# Sensor_Board_2_02_HX711_DS18b2.net
KiCad netlist of a schematic drawn in EAGLE
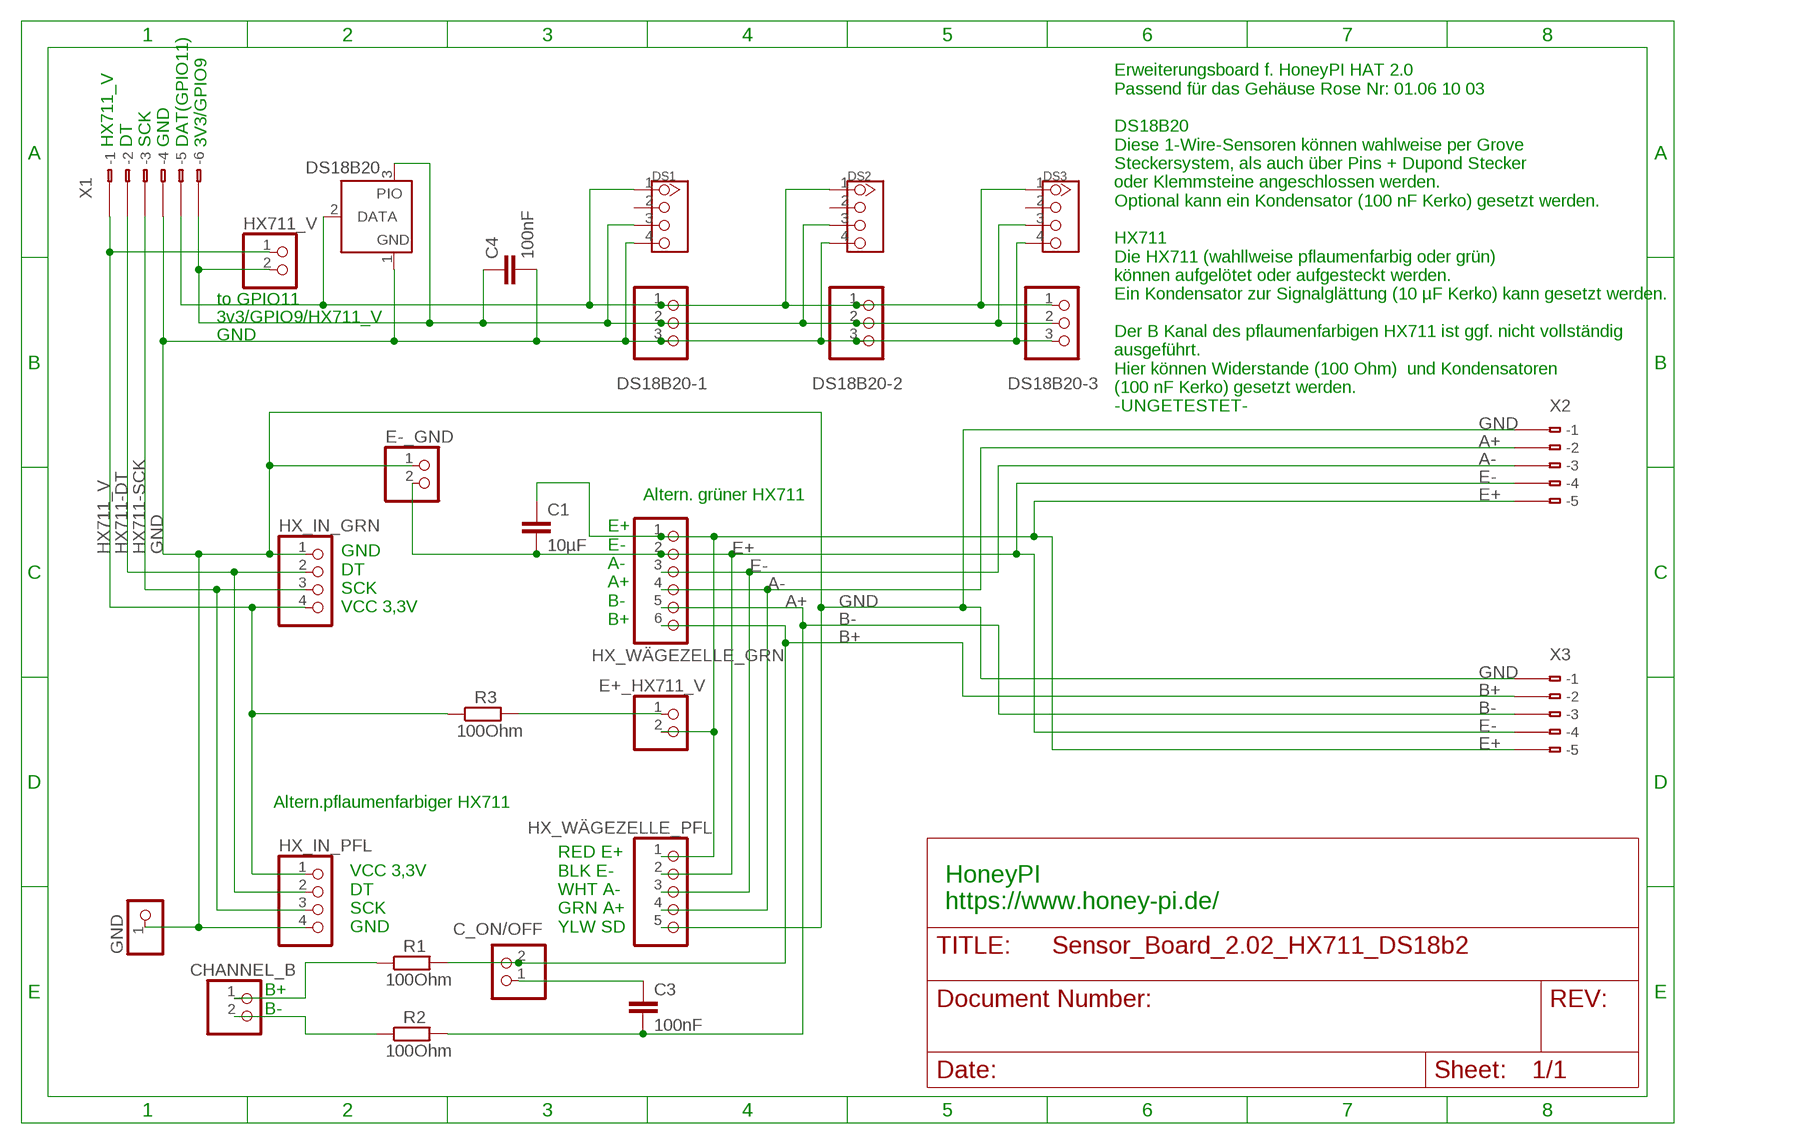
[diagram p0: schematic, sheet 1]

(export (version "E")
  (design (tool "Eeschema 10.0.6"))
  (components
    (comp (ref "C1")
      (value "10µF")
      (footprint "eagle-import:C5B2.5")
      (libsource (lib "eagle-import") (part "C5/2.5"))
    )
    (comp (ref "C3")
      (value "100nF")
      (footprint "eagle-import:C5B2.5")
      (libsource (lib "eagle-import") (part "C5/2.5"))
    )
    (comp (ref "C4")
      (value "100nF")
      (footprint "eagle-import:C5B2.5")
      (libsource (lib "eagle-import") (part "C5/2.5"))
    )
    (comp (ref "CHANNEL_B")
      (value "PINHD-1X2")
      (footprint "eagle-import:1X02")
      (libsource (lib "eagle-import") (part "PINHD-1X2"))
    )
    (comp (ref "C_ON/OFF")
      (value "PINHD-1X2")
      (footprint "eagle-import:1X02")
      (libsource (lib "eagle-import") (part "PINHD-1X2"))
    )
    (comp (ref "DS1")
      (value "TWIG-4P-2.0-2.0")
      (footprint "eagle-import:4P-2.0")
      (libsource (lib "eagle-import") (part "TWIG-4P-2.0-2.0"))
    )
    (comp (ref "DS2")
      (value "TWIG-4P-2.0-2.0")
      (footprint "eagle-import:4P-2.0")
      (libsource (lib "eagle-import") (part "TWIG-4P-2.0-2.0"))
    )
    (comp (ref "DS3")
      (value "TWIG-4P-2.0-2.0")
      (footprint "eagle-import:4P-2.0")
      (libsource (lib "eagle-import") (part "TWIG-4P-2.0-2.0"))
    )
    (comp (ref "DS18B20")
      (value "DS2405")
      (footprint "eagle-import:TO92-")
      (fields (field (name "MF") "DALLAS SEMICONDUCTOR"))
      (libsource (lib "eagle-import") (part "DS2405"))
    )
    (comp (ref "DS18B20-1")
      (value "PINHD-1X3")
      (footprint "eagle-import:1X03")
      (libsource (lib "eagle-import") (part "PINHD-1X3"))
    )
    (comp (ref "DS18B20-2")
      (value "PINHD-1X3")
      (footprint "eagle-import:1X03")
      (libsource (lib "eagle-import") (part "PINHD-1X3"))
    )
    (comp (ref "DS18B20-3")
      (value "PINHD-1X3")
      (footprint "eagle-import:1X03")
      (libsource (lib "eagle-import") (part "PINHD-1X3"))
    )
    (comp (ref "E+_HX711_V")
      (value "PINHD-1X2")
      (footprint "eagle-import:1X02")
      (libsource (lib "eagle-import") (part "PINHD-1X2"))
    )
    (comp (ref "E-_GND")
      (value "PINHD-1X2")
      (footprint "eagle-import:1X02")
      (libsource (lib "eagle-import") (part "PINHD-1X2"))
    )
    (comp (ref "GND")
      (value "PINHD-1X1")
      (footprint "eagle-import:1X01")
      (libsource (lib "eagle-import") (part "PINHD-1X1"))
    )
    (comp (ref "HX711_V")
      (value "PINHD-1X2")
      (footprint "eagle-import:1X02")
      (libsource (lib "eagle-import") (part "PINHD-1X2"))
    )
    (comp (ref "HX_IN_GRN")
      (value "PINHD-1X4")
      (footprint "eagle-import:1X04")
      (libsource (lib "eagle-import") (part "PINHD-1X4"))
    )
    (comp (ref "HX_IN_PFL")
      (value "PINHD-1X4")
      (footprint "eagle-import:1X04")
      (libsource (lib "eagle-import") (part "PINHD-1X4"))
    )
    (comp (ref "HX_WÄGEZELLE_GRN")
      (value "PINHD-1X6")
      (footprint "eagle-import:1X06")
      (libsource (lib "eagle-import") (part "PINHD-1X6"))
    )
    (comp (ref "HX_WÄGEZELLE_PFL")
      (value "PINHD-1X5")
      (footprint "eagle-import:1X05")
      (libsource (lib "eagle-import") (part "PINHD-1X5"))
    )
    (comp (ref "R1")
      (value "100Ohm")
      (footprint "eagle-import:0207_10")
      (libsource (lib "eagle-import") (part "R-EU_0207/10"))
    )
    (comp (ref "R2")
      (value "100Ohm")
      (footprint "eagle-import:0207_10")
      (libsource (lib "eagle-import") (part "R-EU_0207/10"))
    )
    (comp (ref "R3")
      (value "100Ohm")
      (footprint "eagle-import:0207_10")
      (libsource (lib "eagle-import") (part "R-EU_0207/10"))
    )
    (comp (ref "X1")
      (value "233-506")
      (footprint "eagle-import:233-506")
      (fields (field (name "MF") "Wago Corporation") (field (name "MPN") "0233-0506"))
      (libsource (lib "eagle-import") (part "233-506"))
    )
    (comp (ref "X2")
      (value "233-505")
      (footprint "eagle-import:233-505")
      (fields (field (name "MF") "Wago Corporation") (field (name "MPN") "0233-0505"))
      (libsource (lib "eagle-import") (part "233-505"))
    )
    (comp (ref "X3")
      (value "233-505")
      (footprint "eagle-import:233-505")
      (fields (field (name "MF") "Wago Corporation") (field (name "MPN") "0233-0505"))
      (libsource (lib "eagle-import") (part "233-505"))
    )
  )
  (nets
    (net (code "1") (name "/A+") (class "Default")
      (node (ref "HX_WÄGEZELLE_GRN") (pin "4") (pinfunction "4_4") (pintype "passive"))
      (node (ref "HX_WÄGEZELLE_PFL") (pin "4") (pinfunction "4_4") (pintype "passive"))
      (node (ref "X2") (pin "B2") (pinfunction "B-2_B2") (pintype "passive"))
    )
    (net (code "2") (name "/A-") (class "Default")
      (node (ref "HX_WÄGEZELLE_GRN") (pin "3") (pinfunction "3_3") (pintype "passive"))
      (node (ref "HX_WÄGEZELLE_PFL") (pin "3") (pinfunction "3_3") (pintype "passive"))
      (node (ref "X2") (pin "B3") (pinfunction "B-3_B3") (pintype "passive"))
    )
    (net (code "3") (name "/B+") (class "Default")
      (node (ref "C_ON/OFF") (pin "2") (pinfunction "2_2") (pintype "passive"))
      (node (ref "HX_WÄGEZELLE_GRN") (pin "6") (pinfunction "6_6") (pintype "passive"))
      (node (ref "R1") (pin "2") (pinfunction "2_2") (pintype "passive"))
      (node (ref "X3") (pin "B2") (pinfunction "B-2_B2") (pintype "passive"))
    )
    (net (code "4") (name "/B-") (class "Default")
      (node (ref "C3") (pin "2") (pinfunction "2_2") (pintype "passive"))
      (node (ref "HX_WÄGEZELLE_GRN") (pin "5") (pinfunction "5_5") (pintype "passive"))
      (node (ref "R2") (pin "2") (pinfunction "2_2") (pintype "passive"))
      (node (ref "X3") (pin "B3") (pinfunction "B-3_B3") (pintype "passive"))
    )
    (net (code "5") (name "/E+") (class "Default")
      (node (ref "C1") (pin "1") (pinfunction "1_1") (pintype "passive"))
      (node (ref "E+_HX711_V") (pin "2") (pinfunction "2_2") (pintype "passive"))
      (node (ref "HX_WÄGEZELLE_GRN") (pin "1") (pinfunction "1_1") (pintype "passive"))
      (node (ref "HX_WÄGEZELLE_PFL") (pin "1") (pinfunction "1_1") (pintype "passive"))
      (node (ref "X2") (pin "B5") (pinfunction "B-5_B5") (pintype "passive"))
      (node (ref "X3") (pin "B5") (pinfunction "B-5_B5") (pintype "passive"))
    )
    (net (code "6") (name "/E-") (class "Default")
      (node (ref "C1") (pin "2") (pinfunction "2_2") (pintype "passive"))
      (node (ref "E-_GND") (pin "2") (pinfunction "2_2") (pintype "passive"))
      (node (ref "HX_WÄGEZELLE_GRN") (pin "2") (pinfunction "2_2") (pintype "passive"))
      (node (ref "HX_WÄGEZELLE_PFL") (pin "2") (pinfunction "2_2") (pintype "passive"))
      (node (ref "X2") (pin "B4") (pinfunction "B-4_B4") (pintype "passive"))
      (node (ref "X3") (pin "B4") (pinfunction "B-4_B4") (pintype "passive"))
    )
    (net (code "7") (name "/GND") (class "Default")
      (node (ref "C4") (pin "2") (pinfunction "2_2") (pintype "passive"))
      (node (ref "DS1") (pin "4") (pinfunction "4_4") (pintype "bidirectional"))
      (node (ref "DS18B20") (pin "1") (pinfunction "GND_1") (pintype "passive"))
      (node (ref "DS18B20-1") (pin "3") (pinfunction "3_3") (pintype "passive"))
      (node (ref "DS18B20-2") (pin "3") (pinfunction "3_3") (pintype "passive"))
      (node (ref "DS18B20-3") (pin "3") (pinfunction "3_3") (pintype "passive"))
      (node (ref "DS2") (pin "4") (pinfunction "4_4") (pintype "bidirectional"))
      (node (ref "DS3") (pin "4") (pinfunction "4_4") (pintype "bidirectional"))
      (node (ref "E-_GND") (pin "1") (pinfunction "1_1") (pintype "passive"))
      (node (ref "GND") (pin "1") (pinfunction "1_1") (pintype "passive"))
      (node (ref "HX_IN_GRN") (pin "1") (pinfunction "1_1") (pintype "passive"))
      (node (ref "HX_IN_PFL") (pin "4") (pinfunction "4_4") (pintype "passive"))
      (node (ref "HX_WÄGEZELLE_PFL") (pin "5") (pinfunction "5_5") (pintype "passive"))
      (node (ref "X1") (pin "B4") (pinfunction "B-4_B4") (pintype "passive"))
      (node (ref "X2") (pin "B1") (pinfunction "B-1_B1") (pintype "passive"))
      (node (ref "X3") (pin "B1") (pinfunction "B-1_B1") (pintype "passive"))
    )
    (net (code "8") (name "/HX711-DT") (class "Default")
      (node (ref "HX_IN_GRN") (pin "2") (pinfunction "2_2") (pintype "passive"))
      (node (ref "HX_IN_PFL") (pin "2") (pinfunction "2_2") (pintype "passive"))
      (node (ref "X1") (pin "B2") (pinfunction "B-2_B2") (pintype "passive"))
    )
    (net (code "9") (name "/HX711-SCK") (class "Default")
      (node (ref "HX_IN_GRN") (pin "3") (pinfunction "3_3") (pintype "passive"))
      (node (ref "HX_IN_PFL") (pin "3") (pinfunction "3_3") (pintype "passive"))
      (node (ref "X1") (pin "B3") (pinfunction "B-3_B3") (pintype "passive"))
    )
    (net (code "10") (name "/HX711_V") (class "Default")
      (node (ref "HX711_V") (pin "1") (pinfunction "1_1") (pintype "passive"))
      (node (ref "HX_IN_GRN") (pin "4") (pinfunction "4_4") (pintype "passive"))
      (node (ref "HX_IN_PFL") (pin "1") (pinfunction "1_1") (pintype "passive"))
      (node (ref "R3") (pin "1") (pinfunction "1_1") (pintype "passive"))
      (node (ref "X1") (pin "B1") (pinfunction "B-1_B1") (pintype "passive"))
    )
    (net (code "11") (name "Net-(C3-Pad1)") (class "Default")
      (node (ref "C3") (pin "1") (pinfunction "1_1") (pintype "passive"))
      (node (ref "C_ON/OFF") (pin "1") (pinfunction "1_1") (pintype "passive"))
    )
    (net (code "12") (name "Net-(CHANNEL_B-Pad1)") (class "Default")
      (node (ref "CHANNEL_B") (pin "1") (pinfunction "1_1") (pintype "passive"))
      (node (ref "R1") (pin "1") (pinfunction "1_1") (pintype "passive"))
    )
    (net (code "13") (name "Net-(CHANNEL_B-Pad2)") (class "Default")
      (node (ref "CHANNEL_B") (pin "2") (pinfunction "2_2") (pintype "passive"))
      (node (ref "R2") (pin "1") (pinfunction "1_1") (pintype "passive"))
    )
    (net (code "14") (name "Net-(DS18B20-DATA)") (class "Default")
      (node (ref "DS1") (pin "1") (pinfunction "1_1") (pintype "bidirectional"))
      (node (ref "DS18B20") (pin "2") (pinfunction "DATA_2") (pintype "input"))
      (node (ref "DS18B20-1") (pin "1") (pinfunction "1_1") (pintype "passive"))
      (node (ref "DS18B20-2") (pin "1") (pinfunction "1_1") (pintype "passive"))
      (node (ref "DS18B20-3") (pin "1") (pinfunction "1_1") (pintype "passive"))
      (node (ref "DS2") (pin "1") (pinfunction "1_1") (pintype "bidirectional"))
      (node (ref "DS3") (pin "1") (pinfunction "1_1") (pintype "bidirectional"))
      (node (ref "X1") (pin "B5") (pinfunction "B-5_B5") (pintype "passive"))
    )
    (net (code "15") (name "Net-(DS18B20-PIO)") (class "Default")
      (node (ref "C4") (pin "1") (pinfunction "1_1") (pintype "passive"))
      (node (ref "DS1") (pin "3") (pinfunction "3_3") (pintype "bidirectional"))
      (node (ref "DS18B20") (pin "3") (pinfunction "PIO_3") (pintype "passive"))
      (node (ref "DS18B20-1") (pin "2") (pinfunction "2_2") (pintype "passive"))
      (node (ref "DS18B20-2") (pin "2") (pinfunction "2_2") (pintype "passive"))
      (node (ref "DS18B20-3") (pin "2") (pinfunction "2_2") (pintype "passive"))
      (node (ref "DS2") (pin "3") (pinfunction "3_3") (pintype "bidirectional"))
      (node (ref "DS3") (pin "3") (pinfunction "3_3") (pintype "bidirectional"))
      (node (ref "HX711_V") (pin "2") (pinfunction "2_2") (pintype "passive"))
      (node (ref "X1") (pin "B6") (pinfunction "B-6_B6") (pintype "passive"))
    )
    (net (code "16") (name "Net-(E+_HX711_V-Pad1)") (class "Default")
      (node (ref "E+_HX711_V") (pin "1") (pinfunction "1_1") (pintype "passive"))
      (node (ref "R3") (pin "2") (pinfunction "2_2") (pintype "passive"))
    )
    (net (code "17") (name "unconnected-(DS1-Pad2)") (class "Default")
      (node (ref "DS1") (pin "2") (pinfunction "2_2") (pintype "bidirectional"))
    )
    (net (code "18") (name "unconnected-(DS2-Pad2)") (class "Default")
      (node (ref "DS2") (pin "2") (pinfunction "2_2") (pintype "bidirectional"))
    )
    (net (code "19") (name "unconnected-(DS3-Pad2)") (class "Default")
      (node (ref "DS3") (pin "2") (pinfunction "2_2") (pintype "bidirectional"))
    )
    (net (code "20") (name "unconnected-(X1--1-PadA1)") (class "Default")
      (node (ref "X1") (pin "A1") (pinfunction "-1_A1") (pintype "passive"))
    )
    (net (code "21") (name "unconnected-(X1--2-PadA2)") (class "Default")
      (node (ref "X1") (pin "A2") (pinfunction "-2_A2") (pintype "passive"))
    )
    (net (code "22") (name "unconnected-(X1--3-PadA3)") (class "Default")
      (node (ref "X1") (pin "A3") (pinfunction "-3_A3") (pintype "passive"))
    )
    (net (code "23") (name "unconnected-(X1--4-PadA4)") (class "Default")
      (node (ref "X1") (pin "A4") (pinfunction "-4_A4") (pintype "passive"))
    )
    (net (code "24") (name "unconnected-(X1--5-PadA5)") (class "Default")
      (node (ref "X1") (pin "A5") (pinfunction "-5_A5") (pintype "passive"))
    )
    (net (code "25") (name "unconnected-(X1--6-PadA6)") (class "Default")
      (node (ref "X1") (pin "A6") (pinfunction "-6_A6") (pintype "passive"))
    )
    (net (code "26") (name "unconnected-(X2--1-PadA1)") (class "Default")
      (node (ref "X2") (pin "A1") (pinfunction "-1_A1") (pintype "passive"))
    )
    (net (code "27") (name "unconnected-(X2--2-PadA2)") (class "Default")
      (node (ref "X2") (pin "A2") (pinfunction "-2_A2") (pintype "passive"))
    )
    (net (code "28") (name "unconnected-(X2--3-PadA3)") (class "Default")
      (node (ref "X2") (pin "A3") (pinfunction "-3_A3") (pintype "passive"))
    )
    (net (code "29") (name "unconnected-(X2--4-PadA4)") (class "Default")
      (node (ref "X2") (pin "A4") (pinfunction "-4_A4") (pintype "passive"))
    )
    (net (code "30") (name "unconnected-(X2--5-PadA5)") (class "Default")
      (node (ref "X2") (pin "A5") (pinfunction "-5_A5") (pintype "passive"))
    )
    (net (code "31") (name "unconnected-(X3--1-PadA1)") (class "Default")
      (node (ref "X3") (pin "A1") (pinfunction "-1_A1") (pintype "passive"))
    )
    (net (code "32") (name "unconnected-(X3--2-PadA2)") (class "Default")
      (node (ref "X3") (pin "A2") (pinfunction "-2_A2") (pintype "passive"))
    )
    (net (code "33") (name "unconnected-(X3--3-PadA3)") (class "Default")
      (node (ref "X3") (pin "A3") (pinfunction "-3_A3") (pintype "passive"))
    )
    (net (code "34") (name "unconnected-(X3--4-PadA4)") (class "Default")
      (node (ref "X3") (pin "A4") (pinfunction "-4_A4") (pintype "passive"))
    )
    (net (code "35") (name "unconnected-(X3--5-PadA5)") (class "Default")
      (node (ref "X3") (pin "A5") (pinfunction "-5_A5") (pintype "passive"))
    )
  )
)
